# STM8.net
KiCad netlist of a schematic drawn in Altium Designer
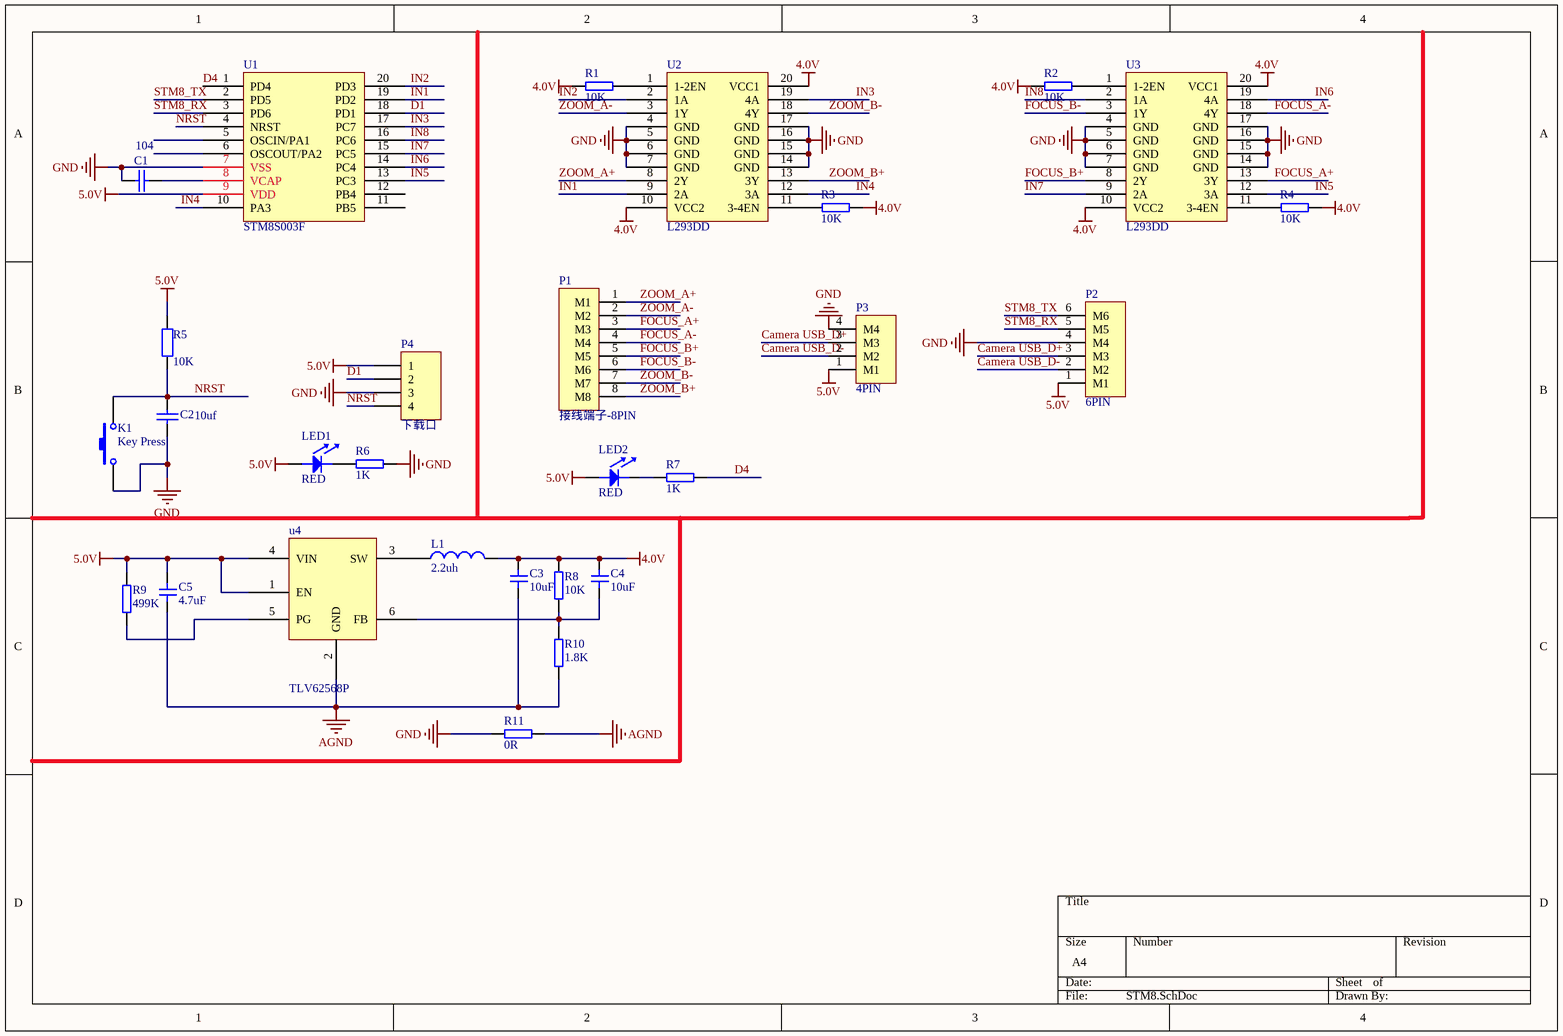
[diagram p0: STM8.SchDoc]

(export (version "E")
  (design (tool "Eeschema 10.0.6"))
  (components
    (comp (ref "C1")
      (value "104")
      (footprint "0805c")
      (description "Capacitor (Semiconductor SIM Model)")
      (fields (field (name "PUBLISHER") "Altium Limited"))
      (libsource (lib "Miscellaneous Devices") (part "Cap Semi"))
    )
    (comp (ref "C2")
      (value "10uf")
      (footprint "0805c")
      (description "Capacitor (Semiconductor SIM Model)")
      (fields (field (name "Comment") "104") (field (name "PUBLISHER") "Altium Limited"))
      (libsource (lib "Miscellaneous Devices") (part "Cap Semi"))
    )
    (comp (ref "C3")
      (value "10uF")
      (footprint "0805C")
      (description "无极贴片电容")
      (libsource (lib "集大电协1.2") (part "Cap1"))
    )
    (comp (ref "C4")
      (value "10uF")
      (footprint "0805C")
      (description "无极贴片电容")
      (libsource (lib "集大电协1.2") (part "Cap1"))
    )
    (comp (ref "C5")
      (value "4.7uF")
      (footprint "0805C")
      (description "无极贴片电容")
      (libsource (lib "集大电协1.2") (part "Cap1"))
    )
    (comp (ref "K1")
      (value "Key Press")
      (footprint "贴片按键")
      (description "贴片按键")
      (libsource (lib "JMU智能车专用元件库") (part "K_Press"))
    )
    (comp (ref "L1")
      (value "2.2uh")
      (footprint "电感（220uh）")
      (description "7*7*4")
      (libsource (lib "JMU智能车专用2.0.6") (part "电感 220uh"))
    )
    (comp (ref "LED1")
      (value "RED")
      (footprint "0805LED")
      (description "发光二极管")
      (libsource (lib "集大电协1.1.2") (part "LED"))
    )
    (comp (ref "LED2")
      (value "RED")
      (footprint "0805LED")
      (description "发光二极管")
      (libsource (lib "集大电协1.1.2") (part "LED"))
    )
    (comp (ref "P1")
      (value "接线端子-8PIN")
      (footprint "MX1.25MM-8P")
      (libsource (lib "集大电协1.1.0") (part "接线端子-8PIN"))
    )
    (comp (ref "P2") (value "6PIN") (footprint "XH2.54-6P") (libsource (lib "集大电协1.2") (part "接线端子-6PIN")))
    (comp (ref "P3")
      (value "4PIN")
      (footprint "XH4/2.54mm/180")
      (libsource (lib "集大电协1.2") (part "接线端子-4PIN"))
    )
    (comp (ref "P4")
      (value "下载口")
      (footprint "Header 4")
      (description "Header, 4-Pin")
      (fields (field (name "PUBLISHER") "Altium Limited"))
      (libsource (lib "Miscellaneous Connectors") (part "Header 4"))
    )
    (comp (ref "R1")
      (value "10K")
      (footprint "0805R")
      (description "电阻")
      (libsource (lib "集大电协1.2") (part "Res"))
    )
    (comp (ref "R2")
      (value "10K")
      (footprint "0805R")
      (description "电阻")
      (libsource (lib "集大电协1.2") (part "Res"))
    )
    (comp (ref "R3")
      (value "10K")
      (footprint "0805R")
      (description "电阻")
      (libsource (lib "集大电协1.2") (part "Res"))
    )
    (comp (ref "R4")
      (value "10K")
      (footprint "0805R")
      (description "电阻")
      (libsource (lib "集大电协1.2") (part "Res"))
    )
    (comp (ref "R5")
      (value "10K")
      (footprint "0805R")
      (description "Resistor")
      (fields (field (name "PUBLISHER") "Altium Limited"))
      (libsource (lib "Miscellaneous Devices") (part "Res2"))
    )
    (comp (ref "R6")
      (value "1K")
      (footprint "0805R")
      (description "电阻")
      (libsource (lib "集大电协1.1.2") (part "Res"))
    )
    (comp (ref "R7")
      (value "1K")
      (footprint "0805R")
      (description "电阻")
      (libsource (lib "集大电协1.1.2") (part "Res"))
    )
    (comp (ref "R8")
      (value "10K")
      (footprint "0805R")
      (description "电阻")
      (libsource (lib "集大电协1.2") (part "Res"))
    )
    (comp (ref "R9")
      (value "499K")
      (footprint "0805R")
      (description "电阻")
      (libsource (lib "集大电协1.2") (part "Res"))
    )
    (comp (ref "R10")
      (value "1.8K")
      (footprint "0805R")
      (description "电阻")
      (libsource (lib "集大电协1.2") (part "Res"))
    )
    (comp (ref "R11")
      (value "0R")
      (footprint "0805R")
      (description "电阻")
      (libsource (lib "集大电协1.2") (part "Res"))
    )
    (comp (ref "U1")
      (value "STM8S003F")
      (footprint "STM8_SOP20")
      (libsource (lib "STM8") (part "Component_1"))
    )
    (comp (ref "U2") (value "L293DD") (footprint "SOP-20M") (libsource (lib "集大电协1.1.2") (part "L293D")))
    (comp (ref "U3") (value "L293DD") (footprint "SOP-20M") (libsource (lib "集大电协1.1.2") (part "L293D")))
    (comp (ref "u4")
      (value "TLV62568P")
      (footprint "TSOT23-6")
      (libsource (lib "集大电协1.2") (part "TLV62568P"))
    )
  )
  (nets
    (net (code "1") (name "/Camera USB_D+") (class "Default")
      (node (ref "P2") (pin "3") (pinfunction "M3_3") (pintype "passive"))
      (node (ref "P3") (pin "3") (pinfunction "M3_3") (pintype "passive"))
    )
    (net (code "2") (name "/Camera USB_D-") (class "Default")
      (node (ref "P2") (pin "2") (pinfunction "M2_2") (pintype "passive"))
      (node (ref "P3") (pin "2") (pinfunction "M2_2") (pintype "passive"))
    )
    (net (code "3") (name "/D1") (class "Default")
      (node (ref "P4") (pin "2") (pinfunction "2_2") (pintype "passive"))
      (node (ref "U1") (pin "18") (pinfunction "PD1_18") (pintype "passive"))
    )
    (net (code "4") (name "/D4") (class "Default")
      (node (ref "R7") (pin "2") (pinfunction "2_2") (pintype "passive"))
      (node (ref "U1") (pin "1") (pinfunction "PD4_1") (pintype "passive"))
    )
    (net (code "5") (name "/FOCUS_A+") (class "Default")
      (node (ref "P1") (pin "3") (pinfunction "M3_3") (pintype "passive"))
      (node (ref "U3") (pin "13") (pinfunction "3Y_13") (pintype "passive"))
    )
    (net (code "6") (name "/FOCUS_A-") (class "Default")
      (node (ref "P1") (pin "4") (pinfunction "M4_4") (pintype "passive"))
      (node (ref "U3") (pin "18") (pinfunction "4Y_18") (pintype "passive"))
    )
    (net (code "7") (name "/FOCUS_B+") (class "Default")
      (node (ref "P1") (pin "5") (pinfunction "M5_5") (pintype "passive"))
      (node (ref "U3") (pin "8") (pinfunction "2Y_8") (pintype "passive"))
    )
    (net (code "8") (name "/FOCUS_B-") (class "Default")
      (node (ref "P1") (pin "6") (pinfunction "M6_6") (pintype "passive"))
      (node (ref "U3") (pin "3") (pinfunction "1Y_3") (pintype "passive"))
    )
    (net (code "9") (name "/IN1") (class "Default")
      (node (ref "U1") (pin "19") (pinfunction "PD2_19") (pintype "passive"))
      (node (ref "U2") (pin "9") (pinfunction "2A_9") (pintype "passive"))
    )
    (net (code "10") (name "/IN2") (class "Default")
      (node (ref "U1") (pin "20") (pinfunction "PD3_20") (pintype "passive"))
      (node (ref "U2") (pin "2") (pinfunction "1A_2") (pintype "passive"))
    )
    (net (code "11") (name "/IN3") (class "Default")
      (node (ref "U1") (pin "17") (pinfunction "PC7_17") (pintype "passive"))
      (node (ref "U2") (pin "19") (pinfunction "4A_19") (pintype "passive"))
    )
    (net (code "12") (name "/IN4") (class "Default")
      (node (ref "U1") (pin "10") (pinfunction "PA3_10") (pintype "passive"))
      (node (ref "U2") (pin "12") (pinfunction "3A_12") (pintype "passive"))
    )
    (net (code "13") (name "/IN5") (class "Default")
      (node (ref "U1") (pin "13") (pinfunction "PC3_13") (pintype "passive"))
      (node (ref "U3") (pin "12") (pinfunction "3A_12") (pintype "passive"))
    )
    (net (code "14") (name "/IN6") (class "Default")
      (node (ref "U1") (pin "14") (pinfunction "PC4_14") (pintype "passive"))
      (node (ref "U3") (pin "19") (pinfunction "4A_19") (pintype "passive"))
    )
    (net (code "15") (name "/IN7") (class "Default")
      (node (ref "U1") (pin "15") (pinfunction "PC5_15") (pintype "passive"))
      (node (ref "U3") (pin "9") (pinfunction "2A_9") (pintype "passive"))
    )
    (net (code "16") (name "/IN8") (class "Default")
      (node (ref "U1") (pin "16") (pinfunction "PC6_16") (pintype "passive"))
      (node (ref "U3") (pin "2") (pinfunction "1A_2") (pintype "passive"))
    )
    (net (code "17") (name "/NRST") (class "Default")
      (node (ref "C2") (pin "2") (pinfunction "2_2") (pintype "passive"))
      (node (ref "K1") (pin "2") (pinfunction "2_2") (pintype "passive"))
      (node (ref "P4") (pin "4") (pinfunction "4_4") (pintype "passive"))
      (node (ref "R5") (pin "1") (pinfunction "1_1") (pintype "passive"))
      (node (ref "U1") (pin "4") (pinfunction "NRST_4") (pintype "passive"))
    )
    (net (code "18") (name "/STM8_RX") (class "Default")
      (node (ref "P2") (pin "5") (pinfunction "M5_5") (pintype "passive"))
      (node (ref "U1") (pin "3") (pinfunction "PD6_3") (pintype "passive"))
    )
    (net (code "19") (name "/STM8_TX") (class "Default")
      (node (ref "P2") (pin "6") (pinfunction "M6_6") (pintype "passive"))
      (node (ref "U1") (pin "2") (pinfunction "PD5_2") (pintype "passive"))
    )
    (net (code "20") (name "/ZOOM_A+") (class "Default")
      (node (ref "P1") (pin "1") (pinfunction "M1_1") (pintype "passive"))
      (node (ref "U2") (pin "8") (pinfunction "2Y_8") (pintype "passive"))
    )
    (net (code "21") (name "/ZOOM_A-") (class "Default")
      (node (ref "P1") (pin "2") (pinfunction "M2_2") (pintype "passive"))
      (node (ref "U2") (pin "3") (pinfunction "1Y_3") (pintype "passive"))
    )
    (net (code "22") (name "/ZOOM_B+") (class "Default")
      (node (ref "P1") (pin "8") (pinfunction "M8_8") (pintype "passive"))
      (node (ref "U2") (pin "13") (pinfunction "3Y_13") (pintype "passive"))
    )
    (net (code "23") (name "/ZOOM_B-") (class "Default")
      (node (ref "P1") (pin "7") (pinfunction "M7_7") (pintype "passive"))
      (node (ref "U2") (pin "18") (pinfunction "4Y_18") (pintype "passive"))
    )
    (net (code "24") (name "4.0V") (class "Default")
      (node (ref "C3") (pin "2") (pinfunction "2_2") (pintype "passive"))
      (node (ref "C4") (pin "2") (pinfunction "2_2") (pintype "passive"))
      (node (ref "L1") (pin "2") (pinfunction "2_2") (pintype "passive"))
      (node (ref "R1") (pin "2") (pinfunction "2_2") (pintype "passive"))
      (node (ref "R2") (pin "2") (pinfunction "2_2") (pintype "passive"))
      (node (ref "R3") (pin "1") (pinfunction "1_1") (pintype "passive"))
      (node (ref "R4") (pin "1") (pinfunction "1_1") (pintype "passive"))
      (node (ref "R8") (pin "2") (pinfunction "2_2") (pintype "passive"))
      (node (ref "U2") (pin "10") (pinfunction "VCC2_10") (pintype "passive"))
      (node (ref "U2") (pin "20") (pinfunction "VCC1_20") (pintype "passive"))
      (node (ref "U3") (pin "10") (pinfunction "VCC2_10") (pintype "passive"))
      (node (ref "U3") (pin "20") (pinfunction "VCC1_20") (pintype "passive"))
    )
    (net (code "25") (name "5.0V") (class "Default")
      (node (ref "C5") (pin "2") (pinfunction "2_2") (pintype "passive"))
      (node (ref "LED1") (pin "1") (pintype "passive"))
      (node (ref "LED2") (pin "1") (pintype "passive"))
      (node (ref "P2") (pin "1") (pinfunction "M1_1") (pintype "passive"))
      (node (ref "P3") (pin "1") (pinfunction "M1_1") (pintype "passive"))
      (node (ref "P4") (pin "1") (pinfunction "1_1") (pintype "passive"))
      (node (ref "R5") (pin "2") (pinfunction "2_2") (pintype "passive"))
      (node (ref "R9") (pin "2") (pinfunction "2_2") (pintype "passive"))
      (node (ref "U1") (pin "9") (pinfunction "VDD_9") (pintype "passive"))
      (node (ref "u4") (pin "1") (pinfunction "EN_1") (pintype "passive"))
      (node (ref "u4") (pin "4") (pinfunction "VIN_4") (pintype "passive"))
    )
    (net (code "26") (name "AGND") (class "Default")
      (node (ref "C3") (pin "1") (pinfunction "1_1") (pintype "passive"))
      (node (ref "C5") (pin "1") (pinfunction "1_1") (pintype "passive"))
      (node (ref "R10") (pin "1") (pinfunction "1_1") (pintype "passive"))
      (node (ref "R11") (pin "2") (pinfunction "2_2") (pintype "passive"))
      (node (ref "u4") (pin "2") (pinfunction "GND_2") (pintype "passive"))
    )
    (net (code "27") (name "GND") (class "Default")
      (node (ref "C1") (pin "1") (pinfunction "1_1") (pintype "passive"))
      (node (ref "C2") (pin "1") (pinfunction "1_1") (pintype "passive"))
      (node (ref "K1") (pin "1") (pinfunction "1_1") (pintype "passive"))
      (node (ref "P2") (pin "4") (pinfunction "M4_4") (pintype "passive"))
      (node (ref "P3") (pin "4") (pinfunction "M4_4") (pintype "passive"))
      (node (ref "P4") (pin "3") (pinfunction "3_3") (pintype "passive"))
      (node (ref "R11") (pin "1") (pinfunction "1_1") (pintype "passive"))
      (node (ref "R6") (pin "2") (pinfunction "2_2") (pintype "passive"))
      (node (ref "U1") (pin "7") (pinfunction "VSS_7") (pintype "passive"))
      (node (ref "U2") (pin "14") (pinfunction "GND_14") (pintype "passive"))
      (node (ref "U2") (pin "15") (pinfunction "GND_15") (pintype "passive"))
      (node (ref "U2") (pin "16") (pinfunction "GND_16") (pintype "passive"))
      (node (ref "U2") (pin "17") (pinfunction "GND_17") (pintype "passive"))
      (node (ref "U2") (pin "4") (pinfunction "GND_4") (pintype "passive"))
      (node (ref "U2") (pin "5") (pinfunction "GND_5") (pintype "passive"))
      (node (ref "U2") (pin "6") (pinfunction "GND_6") (pintype "passive"))
      (node (ref "U2") (pin "7") (pinfunction "GND_7") (pintype "passive"))
      (node (ref "U3") (pin "14") (pinfunction "GND_14") (pintype "passive"))
      (node (ref "U3") (pin "15") (pinfunction "GND_15") (pintype "passive"))
      (node (ref "U3") (pin "16") (pinfunction "GND_16") (pintype "passive"))
      (node (ref "U3") (pin "17") (pinfunction "GND_17") (pintype "passive"))
      (node (ref "U3") (pin "4") (pinfunction "GND_4") (pintype "passive"))
      (node (ref "U3") (pin "5") (pinfunction "GND_5") (pintype "passive"))
      (node (ref "U3") (pin "6") (pinfunction "GND_6") (pintype "passive"))
      (node (ref "U3") (pin "7") (pinfunction "GND_7") (pintype "passive"))
    )
    (net (code "28") (name "Net-(LED1-Pad2)") (class "Default")
      (node (ref "LED1") (pin "2") (pinfunction "2_2") (pintype "passive"))
      (node (ref "R6") (pin "1") (pinfunction "1_1") (pintype "passive"))
    )
    (net (code "29") (name "Net-(LED2-Pad2)") (class "Default")
      (node (ref "LED2") (pin "2") (pinfunction "2_2") (pintype "passive"))
      (node (ref "R7") (pin "1") (pinfunction "1_1") (pintype "passive"))
    )
    (net (code "30") (name "Net-(U1-VCAP)") (class "Default")
      (node (ref "C1") (pin "2") (pinfunction "2_2") (pintype "passive"))
      (node (ref "U1") (pin "8") (pinfunction "VCAP_8") (pintype "passive"))
    )
    (net (code "31") (name "Net-(U2-1-2EN)") (class "Default")
      (node (ref "R1") (pin "1") (pinfunction "1_1") (pintype "passive"))
      (node (ref "U2") (pin "1") (pinfunction "1-2EN_1") (pintype "passive"))
    )
    (net (code "32") (name "Net-(U2-3-4EN)") (class "Default")
      (node (ref "R3") (pin "2") (pinfunction "2_2") (pintype "passive"))
      (node (ref "U2") (pin "11") (pinfunction "3-4EN_11") (pintype "passive"))
    )
    (net (code "33") (name "Net-(U3-1-2EN)") (class "Default")
      (node (ref "R2") (pin "1") (pinfunction "1_1") (pintype "passive"))
      (node (ref "U3") (pin "1") (pinfunction "1-2EN_1") (pintype "passive"))
    )
    (net (code "34") (name "Net-(U3-3-4EN)") (class "Default")
      (node (ref "R4") (pin "2") (pinfunction "2_2") (pintype "passive"))
      (node (ref "U3") (pin "11") (pinfunction "3-4EN_11") (pintype "passive"))
    )
    (net (code "35") (name "Net-(u4-FB)") (class "Default")
      (node (ref "C4") (pin "1") (pinfunction "1_1") (pintype "passive"))
      (node (ref "R10") (pin "2") (pinfunction "2_2") (pintype "passive"))
      (node (ref "R8") (pin "1") (pinfunction "1_1") (pintype "passive"))
      (node (ref "u4") (pin "6") (pinfunction "FB_6") (pintype "passive"))
    )
    (net (code "36") (name "Net-(u4-PG)") (class "Default")
      (node (ref "R9") (pin "1") (pinfunction "1_1") (pintype "passive"))
      (node (ref "u4") (pin "5") (pinfunction "PG_5") (pintype "passive"))
    )
    (net (code "37") (name "Net-(u4-SW)") (class "Default")
      (node (ref "L1") (pin "1") (pinfunction "1_1") (pintype "passive"))
      (node (ref "u4") (pin "3") (pinfunction "SW_3") (pintype "passive"))
    )
    (net (code "38") (name "unconnected-(U1-OSCIN{slash}PA1-Pad5)") (class "Default")
      (node (ref "U1") (pin "5") (pinfunction "OSCIN/PA1_5") (pintype "passive"))
    )
    (net (code "39") (name "unconnected-(U1-OSCOUT{slash}PA2-Pad6)") (class "Default")
      (node (ref "U1") (pin "6") (pinfunction "OSCOUT/PA2_6") (pintype "passive"))
    )
    (net (code "40") (name "unconnected-(U1-PB4-Pad12)") (class "Default")
      (node (ref "U1") (pin "12") (pinfunction "PB4_12") (pintype "passive"))
    )
    (net (code "41") (name "unconnected-(U1-PB5-Pad11)") (class "Default")
      (node (ref "U1") (pin "11") (pinfunction "PB5_11") (pintype "passive"))
    )
  )
)
